# VUE_PIC32_v1_0_Supplies.net
KiCad netlist of a schematic drawn in Altium Designer
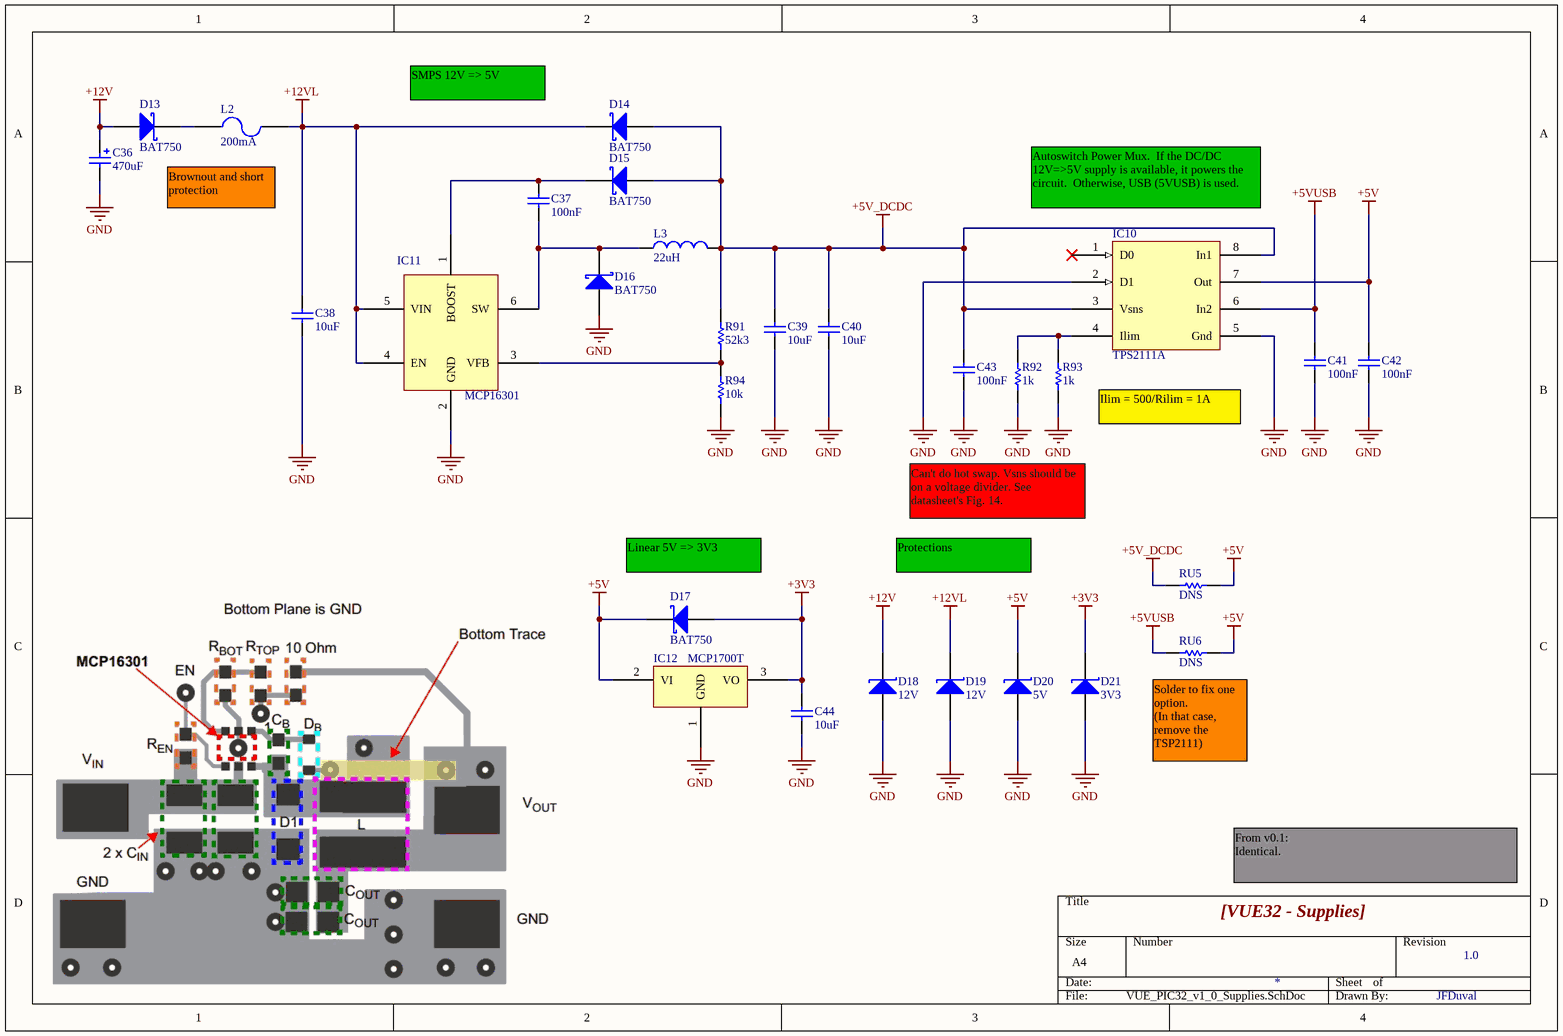
[diagram p0: VUE_PIC32_v1_0_Supplies.SchDoc]

(export (version "E")
  (design (tool "Eeschema 10.0.6"))
  (components
    (comp (ref "C36")
      (value "470uF")
      (footprint "CAP_8D_15H_3_5mm")
      (description "CAP ALUM 470UF 16V 20% RADIAL")
      (fields (field (name "MFG") "Panasonic - ECG") (field (name "MFGPARTNUMBER") "EKY-160ELL471MH15D"))
      (libsource (lib "JFD_Cap") (part "CAP_UNITED_470UF_16V"))
    )
    (comp (ref "C37")
      (value "100nF")
      (footprint "0402C")
      (description "CAP CER 0.1UF 25V Y5V 0402")
      (fields (field (name "MFG") "TDK") (field (name "MFGPARTNUMBER") "C1005Y5V1E104Z"))
      (libsource (lib "JFD_Cap") (part "CAP_TDK_C_0402_100nF_25V"))
    )
    (comp (ref "C38")
      (value "10uF")
      (footprint "0805C")
      (description "CAP CER 10UF 16V Y5V 0805")
      (fields (field (name "MFG") "Murata") (field (name "MFGPARTNUMBER") "GRM21BF51C106ZE15L"))
      (libsource (lib "JFD_Cap") (part "CAP_MURATA_C_0805_10uF_16V"))
    )
    (comp (ref "C39")
      (value "10uF")
      (footprint "0805C")
      (description "CAP CER 10UF 16V Y5V 0805")
      (fields (field (name "MFG") "Murata") (field (name "MFGPARTNUMBER") "GRM21BF51C106ZE15L"))
      (libsource (lib "JFD_Cap") (part "CAP_MURATA_C_0805_10uF_16V"))
    )
    (comp (ref "C40")
      (value "10uF")
      (footprint "0805C")
      (description "CAP CER 10UF 16V Y5V 0805")
      (fields (field (name "MFG") "Murata") (field (name "MFGPARTNUMBER") "GRM21BF51C106ZE15L"))
      (libsource (lib "JFD_Cap") (part "CAP_MURATA_C_0805_10uF_16V"))
    )
    (comp (ref "C41")
      (value "100nF")
      (footprint "0402C")
      (description "CAP CER 0.1UF 25V Y5V 0402")
      (fields (field (name "MFG") "TDK") (field (name "MFGPARTNUMBER") "C1005Y5V1E104Z"))
      (libsource (lib "JFD_Cap") (part "CAP_TDK_C_0402_100nF_25V"))
    )
    (comp (ref "C42")
      (value "100nF")
      (footprint "0402C")
      (description "CAP CER 0.1UF 25V Y5V 0402")
      (fields (field (name "MFG") "TDK") (field (name "MFGPARTNUMBER") "C1005Y5V1E104Z"))
      (libsource (lib "JFD_Cap") (part "CAP_TDK_C_0402_100nF_25V"))
    )
    (comp (ref "C43")
      (value "100nF")
      (footprint "0402C")
      (description "CAP CER 0.1UF 25V Y5V 0402")
      (fields (field (name "MFG") "TDK") (field (name "MFGPARTNUMBER") "C1005Y5V1E104Z"))
      (libsource (lib "JFD_Cap") (part "CAP_TDK_C_0402_100nF_25V"))
    )
    (comp (ref "C44")
      (value "10uF")
      (footprint "0805C")
      (description "CAP CER 10UF 16V Y5V 0805")
      (fields (field (name "MFG") "Murata") (field (name "MFGPARTNUMBER") "GRM21BF51C106ZE15L"))
      (libsource (lib "JFD_Cap") (part "CAP_MURATA_C_0805_10uF_16V"))
    )
    (comp (ref "D13")
      (value "BAT750")
      (footprint "SOT23-3")
      (description "DIODE SCHOTTKY 40V 750MA SOT23-3")
      (fields (field (name "MFG") "Diodes/Zetex") (field (name "MFGPARTNUMBER") "BAT750TA"))
      (libsource (lib "JFD_Semi") (part "DIODE_DIODESINC_BAT750_SCHOTTKY_SOT23_40V_750MA"))
    )
    (comp (ref "D14")
      (value "BAT750")
      (footprint "SOT23-3")
      (description "DIODE SCHOTTKY 40V 750MA SOT23-3")
      (fields (field (name "MFG") "Diodes/Zetex") (field (name "MFGPARTNUMBER") "BAT750TA"))
      (libsource (lib "JFD_Semi") (part "DIODE_DIODESINC_BAT750_SCHOTTKY_SOT23_40V_750MA"))
    )
    (comp (ref "D15")
      (value "BAT750")
      (footprint "SOT23-3")
      (description "DIODE SCHOTTKY 40V 750MA SOT23-3")
      (fields (field (name "MFG") "Diodes/Zetex") (field (name "MFGPARTNUMBER") "BAT750TA"))
      (libsource (lib "JFD_Semi") (part "DIODE_DIODESINC_BAT750_SCHOTTKY_SOT23_40V_750MA"))
    )
    (comp (ref "D16")
      (value "BAT750")
      (footprint "SOT23-3")
      (description "DIODE SCHOTTKY 40V 750MA SOT23-3")
      (fields (field (name "MFG") "Diodes/Zetex") (field (name "MFGPARTNUMBER") "BAT750TA"))
      (libsource (lib "JFD_Semi") (part "DIODE_DIODESINC_BAT750_SCHOTTKY_SOT23_40V_750MA"))
    )
    (comp (ref "D17")
      (value "BAT750")
      (footprint "SOT23-3")
      (description "DIODE SCHOTTKY 40V 750MA SOT23-3")
      (fields (field (name "MFG") "Diodes/Zetex") (field (name "MFGPARTNUMBER") "BAT750TA"))
      (libsource (lib "JFD_Semi") (part "DIODE_DIODESINC_BAT750_SCHOTTKY_SOT23_40V_750MA"))
    )
    (comp (ref "D18")
      (value "12V")
      (footprint "SMA")
      (description "DIODE TVS 12V 400W UNI 5% SMD")
      (fields (field (name "MFG") "Bourns Inc.") (field (name "MFGPARTNUMBER") "SMAJ12A"))
      (libsource (lib "JFD_Semi") (part "DIODE_BOURNS_SMAJ12A_TVS_SMA_12V_400W"))
    )
    (comp (ref "D19")
      (value "12V")
      (footprint "SMA")
      (description "DIODE TVS 12V 400W UNI 5% SMD")
      (fields (field (name "MFG") "Bourns Inc.") (field (name "MFGPARTNUMBER") "SMAJ12A"))
      (libsource (lib "JFD_Semi") (part "DIODE_BOURNS_SMAJ12A_TVS_SMA_12V_400W"))
    )
    (comp (ref "D20")
      (value "5V")
      (footprint "Micro-SMP")
      (description "TVS UNIDIR 100W 5.0V MICROSMP")
      (fields
        (field (name "MFG") "Vishay/General Semiconductor")
        (field (name "MFGPARTNUMBER") "MSP5.0A-M3/89A")
      )
      (libsource (lib "JFD_Semi") (part "DIODE_VISHAY_MSP5_TVS_MICROSMP_5V_100W"))
    )
    (comp (ref "D21")
      (value "3V3")
      (footprint "Micro-SMP")
      (description "TVS UNIDIR 100W 3.3V MICROSMP")
      (fields
        (field (name "MFG") "Vishay/General Semiconductor")
        (field (name "MFGPARTNUMBER") "MSP3V3-M3/89A")
      )
      (libsource (lib "JFD_Semi") (part "DIODE_VISHAY_MSP3V3_TVS_MICROSMP_3V3_100W"))
    )
    (comp (ref "IC10")
      (value "TPS2111A")
      (footprint "TSSOP-8")
      (description "IC AUTOSWITCH POWER MUX 8-TSSOP")
      (fields (field (name "MFG") "Texas Instruments") (field (name "MFGPARTNUMBER") "TPS2111APWR"))
      (libsource (lib "JFD_IC") (part "IC_PMIC_TI_TPS2111_AUTOSWITCH_POWER_MUX"))
    )
    (comp (ref "IC11")
      (value "MCP16301")
      (footprint "SOT23-6")
      (description "IC REG BUCK ADJ 0.6A SOT23-6")
      (fields (field (name "MFG") "Microchip Technology") (field (name "MFGPARTNUMBER") "MCP16301T-I/CHY"))
      (libsource (lib "JFD_IC") (part "IC_DCDC_MICROCHIP_MCP16301"))
    )
    (comp (ref "IC12")
      (value "MCP1700T")
      (footprint "SOT89-3")
      (description "IC REG LDO 3.3V 250MA SOT-89-3")
      (fields (field (name "MFG") "Microchip Technology") (field (name "MFGPARTNUMBER") "MCP1700T-3302E/MB"))
      (libsource (lib "JFD_IC") (part "IC_REG_MICROCHIP_MCP1700_3V3_SOT89"))
    )
    (comp (ref "L2")
      (value "200mA")
      (footprint "1206_PTC")
      (description "PTC RESTTBLE 0.20A 30V CHIP 1206")
      (fields (field (name "MFG") "Bel Fuse Inc") (field (name "MFGPARTNUMBER") "0ZCA0020FF2E"))
      (libsource (lib "JFD_Misc") (part "PTC_BELFUSE_200MA_30V_50MS_1206"))
    )
    (comp (ref "L3")
      (value "22uH")
      (footprint "1812L")
      (description "INDUCTOR WW 22UH .63A 1812 SMD")
      (fields (field (name "MFG") "Wurth Electronics Inc") (field (name "MFGPARTNUMBER") "744045220"))
      (libsource (lib "JFD_Misc") (part "L_WURTH_22uH_630MA_1812"))
    )
    (comp (ref "R91")
      (value "52k3")
      (footprint "0402")
      (description "RES 52.3K OHM 1/10W 1% 0402 SMD")
      (fields (field (name "MFG") "Panasonic - ECG") (field (name "MFGPARTNUMBER") "ERJ-2RKF5232X"))
      (libsource (lib "JFD_Res") (part "RES_PANASONIC_0402_52K3_1PCT"))
    )
    (comp (ref "R92")
      (value "1k")
      (footprint "0402")
      (description "RES 1.00K OHM 1/16W 1% 0402 SMD")
      (fields (field (name "MFG") "Yageo") (field (name "MFGPARTNUMBER") "RC0402FR-071KL"))
      (libsource (lib "JFD_Res") (part "RES_YAGEO_0402_1K_1PCT"))
    )
    (comp (ref "R93")
      (value "1k")
      (footprint "0402")
      (description "RES 1.00K OHM 1/16W 1% 0402 SMD")
      (fields (field (name "MFG") "Yageo") (field (name "MFGPARTNUMBER") "RC0402FR-071KL"))
      (libsource (lib "JFD_Res") (part "RES_YAGEO_0402_1K_1PCT"))
    )
    (comp (ref "R94")
      (value "10k")
      (footprint "0402")
      (description "RES 10.0K OHM 1/16W 1% 0402 SMD")
      (fields (field (name "MFG") "Yageo") (field (name "MFGPARTNUMBER") "RC0402FR-0710KL"))
      (libsource (lib "JFD_Res") (part "RES_YAGEO_0402_10K_1PCT"))
    )
    (comp (ref "RU5")
      (value "DNS")
      (footprint "0603")
      (description "Optional jumper - Do Not Solder")
      (fields (field (name "MFG") "NULL"))
      (libsource (lib "JFD_Res") (part "RES_DO_NOT_SOLDER_DNS_0603"))
    )
    (comp (ref "RU6")
      (value "DNS")
      (footprint "0603")
      (description "Optional jumper - Do Not Solder")
      (fields (field (name "MFG") "NULL"))
      (libsource (lib "JFD_Res") (part "RES_DO_NOT_SOLDER_DNS_0603"))
    )
  )
  (nets
    (net (code "1") (name "+3V3") (class "Default")
      (node (ref "C44") (pin "2") (pinfunction "2_2") (pintype "passive"))
      (node (ref "D17") (pin "1") (pinfunction "A_1") (pintype "passive"))
      (node (ref "D21") (pin "K") (pinfunction "K_K") (pintype "passive"))
      (node (ref "IC12") (pin "3") (pinfunction "VO_3") (pintype "passive"))
    )
    (net (code "2") (name "+5V") (class "Default")
      (node (ref "C42") (pin "2") (pinfunction "2_2") (pintype "passive"))
      (node (ref "D17") (pin "3") (pinfunction "K_3") (pintype "passive"))
      (node (ref "D20") (pin "K") (pinfunction "K_K") (pintype "passive"))
      (node (ref "IC10") (pin "7") (pinfunction "Out_7") (pintype "power_in"))
      (node (ref "IC12") (pin "2") (pinfunction "VI_2") (pintype "passive"))
      (node (ref "RU5") (pin "2") (pinfunction "2_2") (pintype "passive"))
      (node (ref "RU6") (pin "2") (pinfunction "2_2") (pintype "passive"))
    )
    (net (code "3") (name "+5VUSB") (class "Default")
      (node (ref "C41") (pin "2") (pinfunction "2_2") (pintype "passive"))
      (node (ref "IC10") (pin "6") (pinfunction "In2_6") (pintype "power_in"))
      (node (ref "RU6") (pin "1") (pinfunction "1_1") (pintype "passive"))
    )
    (net (code "4") (name "+5V_DCDC") (class "Default")
      (node (ref "C39") (pin "2") (pinfunction "2_2") (pintype "passive"))
      (node (ref "C40") (pin "2") (pinfunction "2_2") (pintype "passive"))
      (node (ref "C43") (pin "2") (pinfunction "2_2") (pintype "passive"))
      (node (ref "D14") (pin "1") (pinfunction "A_1") (pintype "passive"))
      (node (ref "D15") (pin "1") (pinfunction "A_1") (pintype "passive"))
      (node (ref "IC10") (pin "3") (pinfunction "Vsns_3") (pintype "passive"))
      (node (ref "IC10") (pin "8") (pinfunction "In1_8") (pintype "power_in"))
      (node (ref "L3") (pin "2") (pinfunction "2_2") (pintype "passive"))
      (node (ref "R91") (pin "2") (pinfunction "2_2") (pintype "passive"))
      (node (ref "RU5") (pin "1") (pinfunction "1_1") (pintype "passive"))
    )
    (net (code "5") (name "+12V") (class "Default")
      (node (ref "C36") (pin "A") (pinfunction "1_A") (pintype "passive"))
      (node (ref "D13") (pin "1") (pinfunction "A_1") (pintype "passive"))
      (node (ref "D18") (pin "K") (pinfunction "K_K") (pintype "passive"))
    )
    (net (code "6") (name "+12VL") (class "Default")
      (node (ref "C38") (pin "2") (pinfunction "2_2") (pintype "passive"))
      (node (ref "D14") (pin "3") (pinfunction "K_3") (pintype "passive"))
      (node (ref "D19") (pin "K") (pinfunction "K_K") (pintype "passive"))
      (node (ref "IC11") (pin "4") (pinfunction "EN_4") (pintype "passive"))
      (node (ref "IC11") (pin "5") (pinfunction "VIN_5") (pintype "passive"))
      (node (ref "L2") (pin "2") (pinfunction "2_2") (pintype "passive"))
    )
    (net (code "7") (name "GND") (class "Default")
      (node (ref "C36") (pin "K") (pinfunction "2_K") (pintype "passive"))
      (node (ref "C38") (pin "1") (pinfunction "1_1") (pintype "passive"))
      (node (ref "C39") (pin "1") (pinfunction "1_1") (pintype "passive"))
      (node (ref "C40") (pin "1") (pinfunction "1_1") (pintype "passive"))
      (node (ref "C41") (pin "1") (pinfunction "1_1") (pintype "passive"))
      (node (ref "C42") (pin "1") (pinfunction "1_1") (pintype "passive"))
      (node (ref "C43") (pin "1") (pinfunction "1_1") (pintype "passive"))
      (node (ref "C44") (pin "1") (pinfunction "1_1") (pintype "passive"))
      (node (ref "D16") (pin "1") (pinfunction "A_1") (pintype "passive"))
      (node (ref "D18") (pin "A") (pinfunction "A_A") (pintype "passive"))
      (node (ref "D19") (pin "A") (pinfunction "A_A") (pintype "passive"))
      (node (ref "D20") (pin "A") (pinfunction "A_A") (pintype "passive"))
      (node (ref "D21") (pin "A") (pinfunction "A_A") (pintype "passive"))
      (node (ref "IC10") (pin "2") (pinfunction "D1_2") (pintype "input"))
      (node (ref "IC10") (pin "5") (pinfunction "Gnd_5") (pintype "power_in"))
      (node (ref "IC11") (pin "2") (pinfunction "GND_2") (pintype "passive"))
      (node (ref "IC12") (pin "1") (pinfunction "GND_1") (pintype "passive"))
      (node (ref "R92") (pin "1") (pinfunction "1_1") (pintype "passive"))
      (node (ref "R93") (pin "1") (pinfunction "1_1") (pintype "passive"))
      (node (ref "R94") (pin "1") (pinfunction "1_1") (pintype "passive"))
    )
    (net (code "8") (name "Net-(D13-K)") (class "Default")
      (node (ref "D13") (pin "3") (pinfunction "K_3") (pintype "passive"))
      (node (ref "L2") (pin "1") (pinfunction "1_1") (pintype "passive"))
    )
    (net (code "9") (name "Net-(D15-K)") (class "Default")
      (node (ref "C37") (pin "2") (pinfunction "2_2") (pintype "passive"))
      (node (ref "D15") (pin "3") (pinfunction "K_3") (pintype "passive"))
      (node (ref "IC11") (pin "1") (pinfunction "BOOST_1") (pintype "passive"))
    )
    (net (code "10") (name "Net-(D16-K)") (class "Default")
      (node (ref "C37") (pin "1") (pinfunction "1_1") (pintype "passive"))
      (node (ref "D16") (pin "3") (pinfunction "K_3") (pintype "passive"))
      (node (ref "IC11") (pin "6") (pinfunction "SW_6") (pintype "passive"))
      (node (ref "L3") (pin "1") (pinfunction "1_1") (pintype "passive"))
    )
    (net (code "11") (name "Net-(IC10-Ilim)") (class "Default")
      (node (ref "IC10") (pin "4") (pinfunction "Ilim_4") (pintype "passive"))
      (node (ref "R92") (pin "2") (pinfunction "2_2") (pintype "passive"))
      (node (ref "R93") (pin "2") (pinfunction "2_2") (pintype "passive"))
    )
    (net (code "12") (name "Net-(IC11-VFB)") (class "Default")
      (node (ref "IC11") (pin "3") (pinfunction "VFB_3") (pintype "passive"))
      (node (ref "R91") (pin "1") (pinfunction "1_1") (pintype "passive"))
      (node (ref "R94") (pin "2") (pinfunction "2_2") (pintype "passive"))
    )
    (net (code "13") (name "unconnected-(IC10-D0-Pad1)") (class "Default")
      (node (ref "IC10") (pin "1") (pinfunction "D0_1") (pintype "input+no_connect"))
    )
  )
)
